# MCU.net
KiCad netlist of a schematic drawn in Altium Designer
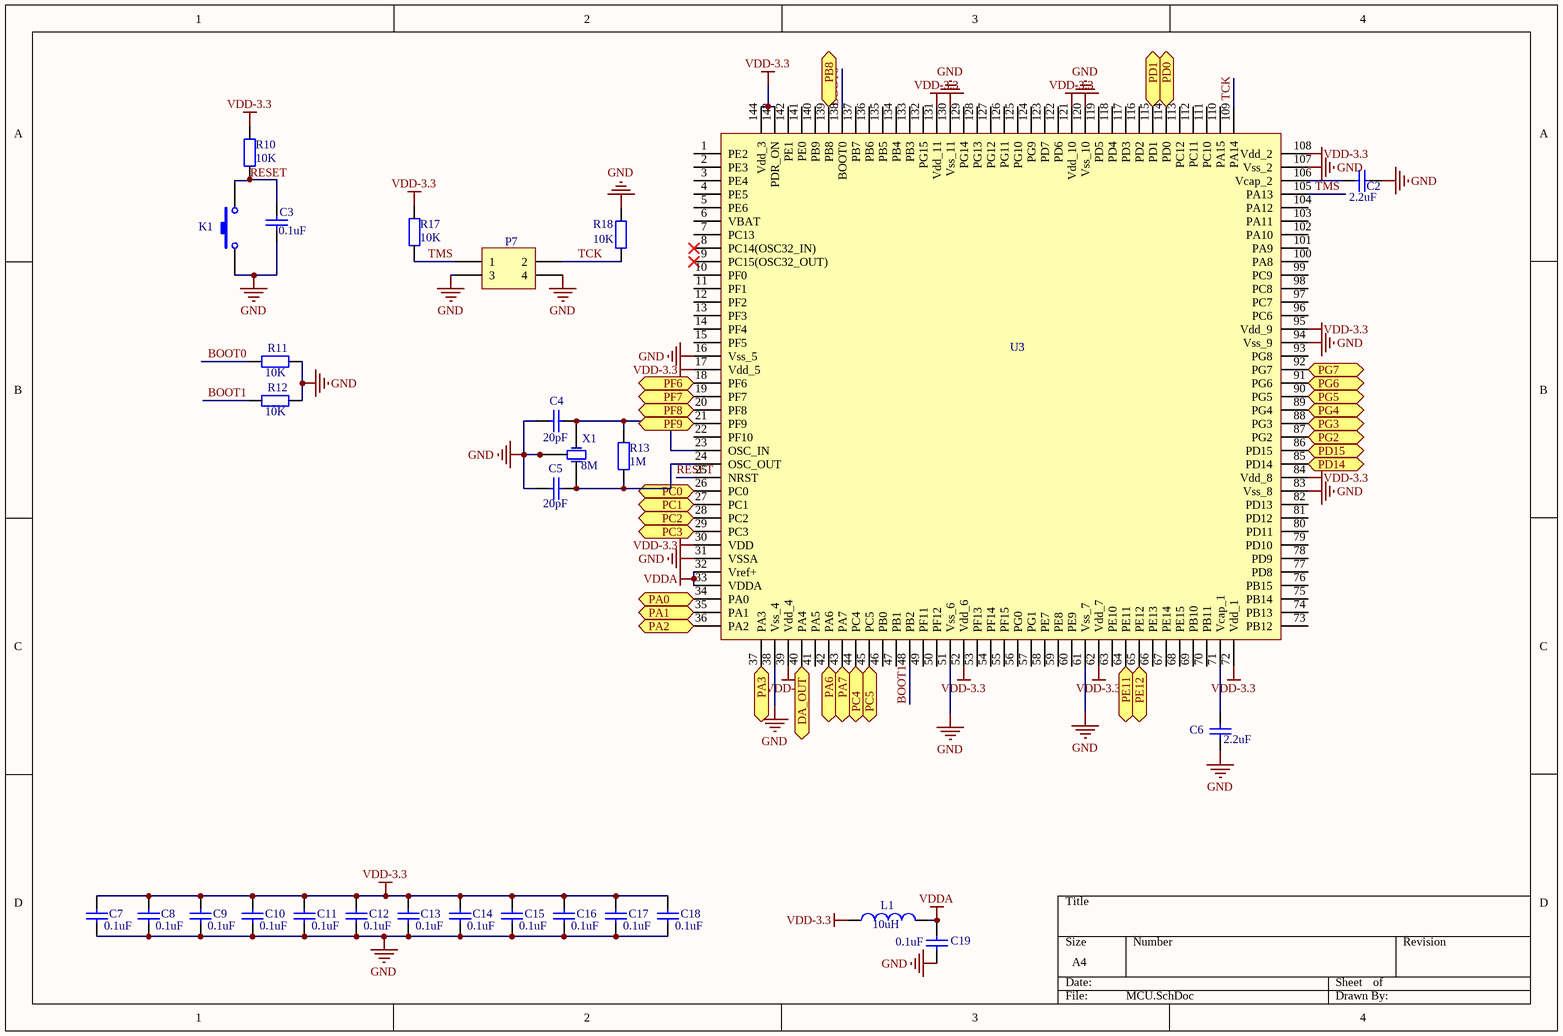
[diagram p0: MCU.SchDoc]

(export (version "E")
  (design (tool "Eeschema 10.0.6"))
  (components
    (comp (ref "C2")
      (value "2.2uF")
      (footprint "0603")
      (fields (field (name "Comment") "Capacitor-0603"))
      (libsource (lib "原理图库") (part "Capacitor-0603"))
    )
    (comp (ref "C3")
      (value "0.1uF")
      (footprint "0603")
      (fields (field (name "Comment") "Capacitor-0805"))
      (libsource (lib "原理图库") (part "Capacitor-0805"))
    )
    (comp (ref "C4")
      (value "20pF")
      (footprint "0603")
      (fields (field (name "Comment") "Capacitor-0603"))
      (libsource (lib "原理图库") (part "Capacitor-0603"))
    )
    (comp (ref "C5")
      (value "20pF")
      (footprint "0603")
      (fields (field (name "Comment") "Capacitor-0603"))
      (libsource (lib "原理图库") (part "Capacitor-0603"))
    )
    (comp (ref "C6")
      (value "2.2uF")
      (footprint "0603")
      (fields (field (name "Comment") "Capacitor-0603"))
      (libsource (lib "原理图库") (part "Capacitor-0603"))
    )
    (comp (ref "C7")
      (value "0.1uF")
      (footprint "0603")
      (fields (field (name "Comment") "Capacitor-0603"))
      (libsource (lib "原理图库") (part "Capacitor-0603"))
    )
    (comp (ref "C8")
      (value "0.1uF")
      (footprint "0603")
      (fields (field (name "Comment") "Capacitor-0603"))
      (libsource (lib "原理图库") (part "Capacitor-0603"))
    )
    (comp (ref "C9")
      (value "0.1uF")
      (footprint "0603")
      (fields (field (name "Comment") "Capacitor-0603"))
      (libsource (lib "原理图库") (part "Capacitor-0603"))
    )
    (comp (ref "C10")
      (value "0.1uF")
      (footprint "0603")
      (fields (field (name "Comment") "Capacitor-0603"))
      (libsource (lib "原理图库") (part "Capacitor-0603"))
    )
    (comp (ref "C11")
      (value "0.1uF")
      (footprint "0603")
      (fields (field (name "Comment") "Capacitor-0603"))
      (libsource (lib "原理图库") (part "Capacitor-0603"))
    )
    (comp (ref "C12")
      (value "0.1uF")
      (footprint "0603")
      (fields (field (name "Comment") "Capacitor-0603"))
      (libsource (lib "原理图库") (part "Capacitor-0603"))
    )
    (comp (ref "C13")
      (value "0.1uF")
      (footprint "0603")
      (fields (field (name "Comment") "Capacitor-0603"))
      (libsource (lib "原理图库") (part "Capacitor-0603"))
    )
    (comp (ref "C14")
      (value "0.1uF")
      (footprint "0603")
      (fields (field (name "Comment") "Capacitor-0603"))
      (libsource (lib "原理图库") (part "Capacitor-0603"))
    )
    (comp (ref "C15")
      (value "0.1uF")
      (footprint "0603")
      (fields (field (name "Comment") "Capacitor-0603"))
      (libsource (lib "原理图库") (part "Capacitor-0603"))
    )
    (comp (ref "C16")
      (value "0.1uF")
      (footprint "0603")
      (fields (field (name "Comment") "Capacitor-0603"))
      (libsource (lib "原理图库") (part "Capacitor-0603"))
    )
    (comp (ref "C17")
      (value "0.1uF")
      (footprint "0603")
      (fields (field (name "Comment") "Capacitor-0603"))
      (libsource (lib "原理图库") (part "Capacitor-0603"))
    )
    (comp (ref "C18")
      (value "0.1uF")
      (footprint "0603")
      (fields (field (name "Comment") "Capacitor-0603"))
      (libsource (lib "原理图库") (part "Capacitor-0603"))
    )
    (comp (ref "C19")
      (value "0.1uF")
      (footprint "0603")
      (fields (field (name "Comment") "Capacitor-0805"))
      (libsource (lib "集成库—大岐") (part "Capacitor-0805"))
    )
    (comp (ref "K1") (value "按键") (footprint "贴片按键") (libsource (lib "原理图库") (part "按键")))
    (comp (ref "L1")
      (value "10uH")
      (footprint "0805")
      (fields (field (name "Comment") "Inductor"))
      (libsource (lib "集成库—大岐") (part "Inductor"))
    )
    (comp (ref "P7")
      (value "Header 2X2")
      (footprint "HDR2X2")
      (description "Header, 2-Pin, Dual row")
      (fields (field (name "PUBLISHER") "Altium Limited"))
      (libsource (lib "Miscellaneous Connectors") (part "Header 2X2"))
    )
    (comp (ref "R10")
      (value "10K")
      (footprint "0603")
      (fields (field (name "Comment") "Resistor-0805"))
      (libsource (lib "") (part "Resistor-0805_1"))
    )
    (comp (ref "R11")
      (value "10K")
      (footprint "0603")
      (fields (field (name "Comment") "Resistor-0805"))
      (libsource (lib "") (part "Resistor-0805_2"))
    )
    (comp (ref "R12")
      (value "10K")
      (footprint "0603")
      (fields (field (name "Comment") "Resistor-0805"))
      (libsource (lib "") (part "Resistor-0805_2"))
    )
    (comp (ref "R13")
      (value "1M")
      (footprint "0603")
      (fields (field (name "Comment") "Resistor-0603"))
      (libsource (lib "原理图库") (part "Resistor-0603"))
    )
    (comp (ref "R17")
      (value "10K")
      (footprint "0603")
      (fields (field (name "Comment") "Resistor-0805"))
      (libsource (lib "原理图库") (part "Resistor-0805"))
    )
    (comp (ref "R18")
      (value "10K")
      (footprint "0603")
      (fields (field (name "Comment") "Resistor-0805"))
      (libsource (lib "") (part "Resistor-0805_1"))
    )
    (comp (ref "U3")
      (value "STM32F407ZET6")
      (footprint "Stm32f407ZET6 - duplicate")
      (fields (field (name "Comment") "STM32F407ZGT6"))
      (libsource (lib "原理图库") (part "STM32F407ZET6"))
    )
    (comp (ref "X1")
      (value "8M")
      (footprint "3225无源晶振")
      (fields (field (name "Comment") "3225无源晶振"))
      (libsource (lib "原理图库") (part "3225无源晶振"))
    )
  )
  (nets
    (net (code "1") (name "/BOOT0") (class "Default")
      (node (ref "R11") (pin "2") (pinfunction "2_2") (pintype "passive"))
      (node (ref "U3") (pin "138") (pinfunction "BOOT0_138") (pintype "passive"))
    )
    (net (code "2") (name "/BOOT1") (class "Default")
      (node (ref "R12") (pin "2") (pinfunction "2_2") (pintype "passive"))
      (node (ref "U3") (pin "48") (pinfunction "PB2_48") (pintype "passive"))
    )
    (net (code "3") (name "/DA_OUT") (class "Default")
      (node (ref "U3") (pin "40") (pinfunction "PA4_40") (pintype "passive"))
    )
    (net (code "4") (name "/PA0") (class "Default")
      (node (ref "U3") (pin "34") (pinfunction "PA0_34") (pintype "passive"))
    )
    (net (code "5") (name "/PA1") (class "Default")
      (node (ref "U3") (pin "35") (pinfunction "PA1_35") (pintype "passive"))
    )
    (net (code "6") (name "/PA2") (class "Default")
      (node (ref "U3") (pin "36") (pinfunction "PA2_36") (pintype "passive"))
    )
    (net (code "7") (name "/PA3") (class "Default")
      (node (ref "U3") (pin "37") (pinfunction "PA3_37") (pintype "passive"))
    )
    (net (code "8") (name "/PA6") (class "Default")
      (node (ref "U3") (pin "42") (pinfunction "PA6_42") (pintype "passive"))
    )
    (net (code "9") (name "/PA7") (class "Default")
      (node (ref "U3") (pin "43") (pinfunction "PA7_43") (pintype "passive"))
    )
    (net (code "10") (name "/PB8") (class "Default")
      (node (ref "U3") (pin "139") (pinfunction "PB8_139") (pintype "passive"))
    )
    (net (code "11") (name "/PC0") (class "Default")
      (node (ref "U3") (pin "26") (pinfunction "PC0_26") (pintype "passive"))
    )
    (net (code "12") (name "/PC1") (class "Default")
      (node (ref "U3") (pin "27") (pinfunction "PC1_27") (pintype "passive"))
    )
    (net (code "13") (name "/PC2") (class "Default")
      (node (ref "U3") (pin "28") (pinfunction "PC2_28") (pintype "passive"))
    )
    (net (code "14") (name "/PC3") (class "Default")
      (node (ref "U3") (pin "29") (pinfunction "PC3_29") (pintype "passive"))
    )
    (net (code "15") (name "/PC4") (class "Default")
      (node (ref "U3") (pin "44") (pinfunction "PC4_44") (pintype "passive"))
    )
    (net (code "16") (name "/PC5") (class "Default")
      (node (ref "U3") (pin "45") (pinfunction "PC5_45") (pintype "passive"))
    )
    (net (code "17") (name "/PD0") (class "Default")
      (node (ref "U3") (pin "114") (pinfunction "PD0_114") (pintype "passive"))
    )
    (net (code "18") (name "/PD1") (class "Default")
      (node (ref "U3") (pin "115") (pinfunction "PD1_115") (pintype "passive"))
    )
    (net (code "19") (name "/PD14") (class "Default")
      (node (ref "U3") (pin "85") (pinfunction "PD14_85") (pintype "passive"))
    )
    (net (code "20") (name "/PD15") (class "Default")
      (node (ref "U3") (pin "86") (pinfunction "PD15_86") (pintype "passive"))
    )
    (net (code "21") (name "/PE11") (class "Default")
      (node (ref "U3") (pin "64") (pinfunction "PE11_64") (pintype "passive"))
    )
    (net (code "22") (name "/PE12") (class "Default")
      (node (ref "U3") (pin "65") (pinfunction "PE12_65") (pintype "passive"))
    )
    (net (code "23") (name "/PF6") (class "Default")
      (node (ref "U3") (pin "18") (pinfunction "PF6_18") (pintype "passive"))
    )
    (net (code "24") (name "/PF7") (class "Default")
      (node (ref "U3") (pin "19") (pinfunction "PF7_19") (pintype "passive"))
    )
    (net (code "25") (name "/PF8") (class "Default")
      (node (ref "U3") (pin "20") (pinfunction "PF8_20") (pintype "passive"))
    )
    (net (code "26") (name "/PF9") (class "Default")
      (node (ref "U3") (pin "21") (pinfunction "PF9_21") (pintype "passive"))
    )
    (net (code "27") (name "/PG2") (class "Default")
      (node (ref "U3") (pin "87") (pinfunction "PG2_87") (pintype "passive"))
    )
    (net (code "28") (name "/PG3") (class "Default")
      (node (ref "U3") (pin "88") (pinfunction "PG3_88") (pintype "passive"))
    )
    (net (code "29") (name "/PG4") (class "Default")
      (node (ref "U3") (pin "89") (pinfunction "PG4_89") (pintype "passive"))
    )
    (net (code "30") (name "/PG5") (class "Default")
      (node (ref "U3") (pin "90") (pinfunction "PG5_90") (pintype "passive"))
    )
    (net (code "31") (name "/PG6") (class "Default")
      (node (ref "U3") (pin "91") (pinfunction "PG6_91") (pintype "passive"))
    )
    (net (code "32") (name "/PG7") (class "Default")
      (node (ref "U3") (pin "92") (pinfunction "PG7_92") (pintype "passive"))
    )
    (net (code "33") (name "/RESET") (class "Default")
      (node (ref "C3") (pin "2") (pinfunction "2_2") (pintype "passive"))
      (node (ref "K1") (pin "2") (pinfunction "2_2") (pintype "passive"))
      (node (ref "R10") (pin "1") (pinfunction "1_1") (pintype "passive"))
      (node (ref "U3") (pin "25") (pinfunction "NRST_25") (pintype "passive"))
    )
    (net (code "34") (name "/TCK") (class "Default")
      (node (ref "P7") (pin "2") (pinfunction "2_2") (pintype "passive"))
      (node (ref "R18") (pin "1") (pinfunction "1_1") (pintype "passive"))
      (node (ref "U3") (pin "109") (pinfunction "PA14_109") (pintype "passive"))
    )
    (net (code "35") (name "/TMS") (class "Default")
      (node (ref "P7") (pin "1") (pinfunction "1_1") (pintype "passive"))
      (node (ref "R17") (pin "2") (pinfunction "2_2") (pintype "passive"))
      (node (ref "U3") (pin "105") (pinfunction "PA13_105") (pintype "passive"))
    )
    (net (code "36") (name "GND") (class "Default")
      (node (ref "C10") (pin "1") (pinfunction "1_1") (pintype "passive"))
      (node (ref "C11") (pin "1") (pinfunction "1_1") (pintype "passive"))
      (node (ref "C12") (pin "1") (pinfunction "1_1") (pintype "passive"))
      (node (ref "C13") (pin "1") (pinfunction "1_1") (pintype "passive"))
      (node (ref "C14") (pin "1") (pinfunction "1_1") (pintype "passive"))
      (node (ref "C15") (pin "1") (pinfunction "1_1") (pintype "passive"))
      (node (ref "C16") (pin "1") (pinfunction "1_1") (pintype "passive"))
      (node (ref "C17") (pin "1") (pinfunction "1_1") (pintype "passive"))
      (node (ref "C18") (pin "1") (pinfunction "1_1") (pintype "passive"))
      (node (ref "C19") (pin "1") (pinfunction "1_1") (pintype "passive"))
      (node (ref "C2") (pin "2") (pinfunction "2_2") (pintype "passive"))
      (node (ref "C3") (pin "1") (pinfunction "1_1") (pintype "passive"))
      (node (ref "C4") (pin "1") (pinfunction "1_1") (pintype "passive"))
      (node (ref "C5") (pin "1") (pinfunction "1_1") (pintype "passive"))
      (node (ref "C6") (pin "1") (pinfunction "1_1") (pintype "passive"))
      (node (ref "C7") (pin "1") (pinfunction "1_1") (pintype "passive"))
      (node (ref "C8") (pin "1") (pinfunction "1_1") (pintype "passive"))
      (node (ref "C9") (pin "1") (pinfunction "1_1") (pintype "passive"))
      (node (ref "K1") (pin "1") (pinfunction "1_1") (pintype "passive"))
      (node (ref "P7") (pin "3") (pinfunction "3_3") (pintype "passive"))
      (node (ref "P7") (pin "4") (pinfunction "4_4") (pintype "passive"))
      (node (ref "R11") (pin "1") (pinfunction "1_1") (pintype "passive"))
      (node (ref "R12") (pin "1") (pinfunction "1_1") (pintype "passive"))
      (node (ref "R18") (pin "2") (pinfunction "2_2") (pintype "passive"))
      (node (ref "U3") (pin "107") (pinfunction "Vss_2_107") (pintype "passive"))
      (node (ref "U3") (pin "120") (pinfunction "Vss_10_120") (pintype "passive"))
      (node (ref "U3") (pin "130") (pinfunction "Vss_11_130") (pintype "passive"))
      (node (ref "U3") (pin "16") (pinfunction "Vss_5_16") (pintype "passive"))
      (node (ref "U3") (pin "31") (pinfunction "VSSA_31") (pintype "passive"))
      (node (ref "U3") (pin "38") (pinfunction "Vss_4_38") (pintype "passive"))
      (node (ref "U3") (pin "51") (pinfunction "Vss_6_51") (pintype "passive"))
      (node (ref "U3") (pin "61") (pinfunction "Vss_7_61") (pintype "passive"))
      (node (ref "U3") (pin "83") (pinfunction "Vss_8_83") (pintype "passive"))
      (node (ref "U3") (pin "94") (pinfunction "Vss_9_94") (pintype "passive"))
      (node (ref "X1") (pin "2") (pinfunction "GND_2") (pintype "passive"))
      (node (ref "X1") (pin "4") (pinfunction "GND_4") (pintype "passive"))
    )
    (net (code "37") (name "Net-(U3-OSC_IN)") (class "Default")
      (node (ref "C4") (pin "2") (pinfunction "2_2") (pintype "passive"))
      (node (ref "R13") (pin "2") (pinfunction "2_2") (pintype "passive"))
      (node (ref "U3") (pin "23") (pinfunction "OSC_IN_23") (pintype "passive"))
      (node (ref "X1") (pin "1") (pinfunction "OSC1_1") (pintype "passive"))
    )
    (net (code "38") (name "Net-(U3-OSC_OUT)") (class "Default")
      (node (ref "C5") (pin "2") (pinfunction "2_2") (pintype "passive"))
      (node (ref "R13") (pin "1") (pinfunction "1_1") (pintype "passive"))
      (node (ref "U3") (pin "24") (pinfunction "OSC_OUT_24") (pintype "passive"))
      (node (ref "X1") (pin "3") (pinfunction "OSC2_3") (pintype "passive"))
    )
    (net (code "39") (name "Net-(U3-Vcap_1)") (class "Default")
      (node (ref "C6") (pin "2") (pinfunction "2_2") (pintype "passive"))
      (node (ref "U3") (pin "71") (pinfunction "Vcap_1_71") (pintype "passive"))
    )
    (net (code "40") (name "Net-(U3-Vcap_2)") (class "Default")
      (node (ref "C2") (pin "1") (pinfunction "1_1") (pintype "passive"))
      (node (ref "U3") (pin "106") (pinfunction "Vcap_2_106") (pintype "passive"))
    )
    (net (code "41") (name "VDD-3.3") (class "Default")
      (node (ref "C10") (pin "2") (pinfunction "2_2") (pintype "passive"))
      (node (ref "C11") (pin "2") (pinfunction "2_2") (pintype "passive"))
      (node (ref "C12") (pin "2") (pinfunction "2_2") (pintype "passive"))
      (node (ref "C13") (pin "2") (pinfunction "2_2") (pintype "passive"))
      (node (ref "C14") (pin "2") (pinfunction "2_2") (pintype "passive"))
      (node (ref "C15") (pin "2") (pinfunction "2_2") (pintype "passive"))
      (node (ref "C16") (pin "2") (pinfunction "2_2") (pintype "passive"))
      (node (ref "C17") (pin "2") (pinfunction "2_2") (pintype "passive"))
      (node (ref "C18") (pin "2") (pinfunction "2_2") (pintype "passive"))
      (node (ref "C7") (pin "2") (pinfunction "2_2") (pintype "passive"))
      (node (ref "C8") (pin "2") (pinfunction "2_2") (pintype "passive"))
      (node (ref "C9") (pin "2") (pinfunction "2_2") (pintype "passive"))
      (node (ref "L1") (pin "1") (pinfunction "1_1") (pintype "passive"))
      (node (ref "R10") (pin "2") (pinfunction "2_2") (pintype "passive"))
      (node (ref "R17") (pin "1") (pinfunction "1_1") (pintype "passive"))
      (node (ref "U3") (pin "108") (pinfunction "Vdd_2_108") (pintype "passive"))
      (node (ref "U3") (pin "121") (pinfunction "Vdd_10_121") (pintype "passive"))
      (node (ref "U3") (pin "131") (pinfunction "Vdd_11_131") (pintype "passive"))
      (node (ref "U3") (pin "143") (pinfunction "PDR_ON_143") (pintype "passive"))
      (node (ref "U3") (pin "144") (pinfunction "Vdd_3_144") (pintype "passive"))
      (node (ref "U3") (pin "17") (pinfunction "Vdd_5_17") (pintype "passive"))
      (node (ref "U3") (pin "30") (pinfunction "VDD_30") (pintype "passive"))
      (node (ref "U3") (pin "39") (pinfunction "Vdd_4_39") (pintype "passive"))
      (node (ref "U3") (pin "52") (pinfunction "Vdd_6_52") (pintype "passive"))
      (node (ref "U3") (pin "62") (pinfunction "Vdd_7_62") (pintype "passive"))
      (node (ref "U3") (pin "72") (pinfunction "Vdd_1_72") (pintype "passive"))
      (node (ref "U3") (pin "84") (pinfunction "Vdd_8_84") (pintype "passive"))
      (node (ref "U3") (pin "95") (pinfunction "Vdd_9_95") (pintype "passive"))
    )
    (net (code "42") (name "VDDA") (class "Default")
      (node (ref "C19") (pin "2") (pinfunction "2_2") (pintype "passive"))
      (node (ref "L1") (pin "2") (pinfunction "2_2") (pintype "passive"))
      (node (ref "U3") (pin "32") (pinfunction "Vref+_32") (pintype "passive"))
      (node (ref "U3") (pin "33") (pinfunction "VDDA_33") (pintype "passive"))
    )
    (net (code "43") (name "unconnected-(U3-PA5-Pad41)") (class "Default")
      (node (ref "U3") (pin "41") (pinfunction "PA5_41") (pintype "passive"))
    )
    (net (code "44") (name "unconnected-(U3-PA8-Pad100)") (class "Default")
      (node (ref "U3") (pin "100") (pinfunction "PA8_100") (pintype "passive"))
    )
    (net (code "45") (name "unconnected-(U3-PA9-Pad101)") (class "Default")
      (node (ref "U3") (pin "101") (pinfunction "PA9_101") (pintype "passive"))
    )
    (net (code "46") (name "unconnected-(U3-PA10-Pad102)") (class "Default")
      (node (ref "U3") (pin "102") (pinfunction "PA10_102") (pintype "passive"))
    )
    (net (code "47") (name "unconnected-(U3-PA11-Pad103)") (class "Default")
      (node (ref "U3") (pin "103") (pinfunction "PA11_103") (pintype "passive"))
    )
    (net (code "48") (name "unconnected-(U3-PA12-Pad104)") (class "Default")
      (node (ref "U3") (pin "104") (pinfunction "PA12_104") (pintype "passive"))
    )
    (net (code "49") (name "unconnected-(U3-PA15-Pad110)") (class "Default")
      (node (ref "U3") (pin "110") (pinfunction "PA15_110") (pintype "passive"))
    )
    (net (code "50") (name "unconnected-(U3-PB0-Pad46)") (class "Default")
      (node (ref "U3") (pin "46") (pinfunction "PB0_46") (pintype "passive"))
    )
    (net (code "51") (name "unconnected-(U3-PB1-Pad47)") (class "Default")
      (node (ref "U3") (pin "47") (pinfunction "PB1_47") (pintype "passive"))
    )
    (net (code "52") (name "unconnected-(U3-PB3-Pad133)") (class "Default")
      (node (ref "U3") (pin "133") (pinfunction "PB3_133") (pintype "passive"))
    )
    (net (code "53") (name "unconnected-(U3-PB4-Pad134)") (class "Default")
      (node (ref "U3") (pin "134") (pinfunction "PB4_134") (pintype "passive"))
    )
    (net (code "54") (name "unconnected-(U3-PB5-Pad135)") (class "Default")
      (node (ref "U3") (pin "135") (pinfunction "PB5_135") (pintype "passive"))
    )
    (net (code "55") (name "unconnected-(U3-PB6-Pad136)") (class "Default")
      (node (ref "U3") (pin "136") (pinfunction "PB6_136") (pintype "passive"))
    )
    (net (code "56") (name "unconnected-(U3-PB7-Pad137)") (class "Default")
      (node (ref "U3") (pin "137") (pinfunction "PB7_137") (pintype "passive"))
    )
    (net (code "57") (name "unconnected-(U3-PB9-Pad140)") (class "Default")
      (node (ref "U3") (pin "140") (pinfunction "PB9_140") (pintype "passive"))
    )
    (net (code "58") (name "unconnected-(U3-PB10-Pad69)") (class "Default")
      (node (ref "U3") (pin "69") (pinfunction "PB10_69") (pintype "passive"))
    )
    (net (code "59") (name "unconnected-(U3-PB11-Pad70)") (class "Default")
      (node (ref "U3") (pin "70") (pinfunction "PB11_70") (pintype "passive"))
    )
    (net (code "60") (name "unconnected-(U3-PB12-Pad73)") (class "Default")
      (node (ref "U3") (pin "73") (pinfunction "PB12_73") (pintype "passive"))
    )
    (net (code "61") (name "unconnected-(U3-PB13-Pad74)") (class "Default")
      (node (ref "U3") (pin "74") (pinfunction "PB13_74") (pintype "passive"))
    )
    (net (code "62") (name "unconnected-(U3-PB14-Pad75)") (class "Default")
      (node (ref "U3") (pin "75") (pinfunction "PB14_75") (pintype "passive"))
    )
    (net (code "63") (name "unconnected-(U3-PB15-Pad76)") (class "Default")
      (node (ref "U3") (pin "76") (pinfunction "PB15_76") (pintype "passive"))
    )
    (net (code "64") (name "unconnected-(U3-PC6-Pad96)") (class "Default")
      (node (ref "U3") (pin "96") (pinfunction "PC6_96") (pintype "passive"))
    )
    (net (code "65") (name "unconnected-(U3-PC7-Pad97)") (class "Default")
      (node (ref "U3") (pin "97") (pinfunction "PC7_97") (pintype "passive"))
    )
    (net (code "66") (name "unconnected-(U3-PC8-Pad98)") (class "Default")
      (node (ref "U3") (pin "98") (pinfunction "PC8_98") (pintype "passive"))
    )
    (net (code "67") (name "unconnected-(U3-PC9-Pad99)") (class "Default")
      (node (ref "U3") (pin "99") (pinfunction "PC9_99") (pintype "passive"))
    )
    (net (code "68") (name "unconnected-(U3-PC10-Pad111)") (class "Default")
      (node (ref "U3") (pin "111") (pinfunction "PC10_111") (pintype "passive"))
    )
    (net (code "69") (name "unconnected-(U3-PC11-Pad112)") (class "Default")
      (node (ref "U3") (pin "112") (pinfunction "PC11_112") (pintype "passive"))
    )
    (net (code "70") (name "unconnected-(U3-PC12-Pad113)") (class "Default")
      (node (ref "U3") (pin "113") (pinfunction "PC12_113") (pintype "passive"))
    )
    (net (code "71") (name "unconnected-(U3-PC13-Pad7)") (class "Default")
      (node (ref "U3") (pin "7") (pinfunction "PC13_7") (pintype "passive"))
    )
    (net (code "72") (name "unconnected-(U3-PC14(OSC32_IN)-Pad8)") (class "Default")
      (node (ref "U3") (pin "8") (pinfunction "PC14(OSC32_IN)_8") (pintype "passive+no_connect"))
    )
    (net (code "73") (name "unconnected-(U3-PC15(OSC32_OUT)-Pad9)") (class "Default")
      (node (ref "U3") (pin "9") (pinfunction "PC15(OSC32_OUT)_9") (pintype "passive+no_connect"))
    )
    (net (code "74") (name "unconnected-(U3-PD2-Pad116)") (class "Default")
      (node (ref "U3") (pin "116") (pinfunction "PD2_116") (pintype "passive"))
    )
    (net (code "75") (name "unconnected-(U3-PD3-Pad117)") (class "Default")
      (node (ref "U3") (pin "117") (pinfunction "PD3_117") (pintype "passive"))
    )
    (net (code "76") (name "unconnected-(U3-PD4-Pad118)") (class "Default")
      (node (ref "U3") (pin "118") (pinfunction "PD4_118") (pintype "passive"))
    )
    (net (code "77") (name "unconnected-(U3-PD5-Pad119)") (class "Default")
      (node (ref "U3") (pin "119") (pinfunction "PD5_119") (pintype "passive"))
    )
    (net (code "78") (name "unconnected-(U3-PD6-Pad122)") (class "Default")
      (node (ref "U3") (pin "122") (pinfunction "PD6_122") (pintype "passive"))
    )
    (net (code "79") (name "unconnected-(U3-PD7-Pad123)") (class "Default")
      (node (ref "U3") (pin "123") (pinfunction "PD7_123") (pintype "passive"))
    )
    (net (code "80") (name "unconnected-(U3-PD8-Pad77)") (class "Default")
      (node (ref "U3") (pin "77") (pinfunction "PD8_77") (pintype "passive"))
    )
    (net (code "81") (name "unconnected-(U3-PD9-Pad78)") (class "Default")
      (node (ref "U3") (pin "78") (pinfunction "PD9_78") (pintype "passive"))
    )
    (net (code "82") (name "unconnected-(U3-PD10-Pad79)") (class "Default")
      (node (ref "U3") (pin "79") (pinfunction "PD10_79") (pintype "passive"))
    )
    (net (code "83") (name "unconnected-(U3-PD11-Pad80)") (class "Default")
      (node (ref "U3") (pin "80") (pinfunction "PD11_80") (pintype "passive"))
    )
    (net (code "84") (name "unconnected-(U3-PD12-Pad81)") (class "Default")
      (node (ref "U3") (pin "81") (pinfunction "PD12_81") (pintype "passive"))
    )
    (net (code "85") (name "unconnected-(U3-PD13-Pad82)") (class "Default")
      (node (ref "U3") (pin "82") (pinfunction "PD13_82") (pintype "passive"))
    )
    (net (code "86") (name "unconnected-(U3-PE0-Pad141)") (class "Default")
      (node (ref "U3") (pin "141") (pinfunction "PE0_141") (pintype "passive"))
    )
    (net (code "87") (name "unconnected-(U3-PE1-Pad142)") (class "Default")
      (node (ref "U3") (pin "142") (pinfunction "PE1_142") (pintype "passive"))
    )
    (net (code "88") (name "unconnected-(U3-PE2-Pad1)") (class "Default")
      (node (ref "U3") (pin "1") (pinfunction "PE2_1") (pintype "passive"))
    )
    (net (code "89") (name "unconnected-(U3-PE3-Pad2)") (class "Default")
      (node (ref "U3") (pin "2") (pinfunction "PE3_2") (pintype "passive"))
    )
    (net (code "90") (name "unconnected-(U3-PE4-Pad3)") (class "Default")
      (node (ref "U3") (pin "3") (pinfunction "PE4_3") (pintype "passive"))
    )
    (net (code "91") (name "unconnected-(U3-PE5-Pad4)") (class "Default")
      (node (ref "U3") (pin "4") (pinfunction "PE5_4") (pintype "passive"))
    )
    (net (code "92") (name "unconnected-(U3-PE6-Pad5)") (class "Default")
      (node (ref "U3") (pin "5") (pinfunction "PE6_5") (pintype "passive"))
    )
    (net (code "93") (name "unconnected-(U3-PE7-Pad58)") (class "Default")
      (node (ref "U3") (pin "58") (pinfunction "PE7_58") (pintype "passive"))
    )
    (net (code "94") (name "unconnected-(U3-PE8-Pad59)") (class "Default")
      (node (ref "U3") (pin "59") (pinfunction "PE8_59") (pintype "passive"))
    )
    (net (code "95") (name "unconnected-(U3-PE9-Pad60)") (class "Default")
      (node (ref "U3") (pin "60") (pinfunction "PE9_60") (pintype "passive"))
    )
    (net (code "96") (name "unconnected-(U3-PE10-Pad63)") (class "Default")
      (node (ref "U3") (pin "63") (pinfunction "PE10_63") (pintype "passive"))
    )
    (net (code "97") (name "unconnected-(U3-PE13-Pad66)") (class "Default")
      (node (ref "U3") (pin "66") (pinfunction "PE13_66") (pintype "passive"))
    )
    (net (code "98") (name "unconnected-(U3-PE14-Pad67)") (class "Default")
      (node (ref "U3") (pin "67") (pinfunction "PE14_67") (pintype "passive"))
    )
    (net (code "99") (name "unconnected-(U3-PE15-Pad68)") (class "Default")
      (node (ref "U3") (pin "68") (pinfunction "PE15_68") (pintype "passive"))
    )
    (net (code "100") (name "unconnected-(U3-PF0-Pad10)") (class "Default")
      (node (ref "U3") (pin "10") (pinfunction "PF0_10") (pintype "passive"))
    )
    (net (code "101") (name "unconnected-(U3-PF1-Pad11)") (class "Default")
      (node (ref "U3") (pin "11") (pinfunction "PF1_11") (pintype "passive"))
    )
    (net (code "102") (name "unconnected-(U3-PF2-Pad12)") (class "Default")
      (node (ref "U3") (pin "12") (pinfunction "PF2_12") (pintype "passive"))
    )
    (net (code "103") (name "unconnected-(U3-PF3-Pad13)") (class "Default")
      (node (ref "U3") (pin "13") (pinfunction "PF3_13") (pintype "passive"))
    )
    (net (code "104") (name "unconnected-(U3-PF4-Pad14)") (class "Default")
      (node (ref "U3") (pin "14") (pinfunction "PF4_14") (pintype "passive"))
    )
    (net (code "105") (name "unconnected-(U3-PF5-Pad15)") (class "Default")
      (node (ref "U3") (pin "15") (pinfunction "PF5_15") (pintype "passive"))
    )
    (net (code "106") (name "unconnected-(U3-PF10-Pad22)") (class "Default")
      (node (ref "U3") (pin "22") (pinfunction "PF10_22") (pintype "passive"))
    )
    (net (code "107") (name "unconnected-(U3-PF11-Pad49)") (class "Default")
      (node (ref "U3") (pin "49") (pinfunction "PF11_49") (pintype "passive"))
    )
    (net (code "108") (name "unconnected-(U3-PF12-Pad50)") (class "Default")
      (node (ref "U3") (pin "50") (pinfunction "PF12_50") (pintype "passive"))
    )
    (net (code "109") (name "unconnected-(U3-PF13-Pad53)") (class "Default")
      (node (ref "U3") (pin "53") (pinfunction "PF13_53") (pintype "passive"))
    )
    (net (code "110") (name "unconnected-(U3-PF14-Pad54)") (class "Default")
      (node (ref "U3") (pin "54") (pinfunction "PF14_54") (pintype "passive"))
    )
    (net (code "111") (name "unconnected-(U3-PF15-Pad55)") (class "Default")
      (node (ref "U3") (pin "55") (pinfunction "PF15_55") (pintype "passive"))
    )
    (net (code "112") (name "unconnected-(U3-PG0-Pad56)") (class "Default")
      (node (ref "U3") (pin "56") (pinfunction "PG0_56") (pintype "passive"))
    )
    (net (code "113") (name "unconnected-(U3-PG1-Pad57)") (class "Default")
      (node (ref "U3") (pin "57") (pinfunction "PG1_57") (pintype "passive"))
    )
    (net (code "114") (name "unconnected-(U3-PG8-Pad93)") (class "Default")
      (node (ref "U3") (pin "93") (pinfunction "PG8_93") (pintype "passive"))
    )
    (net (code "115") (name "unconnected-(U3-PG9-Pad124)") (class "Default")
      (node (ref "U3") (pin "124") (pinfunction "PG9_124") (pintype "passive"))
    )
    (net (code "116") (name "unconnected-(U3-PG10-Pad125)") (class "Default")
      (node (ref "U3") (pin "125") (pinfunction "PG10_125") (pintype "passive"))
    )
    (net (code "117") (name "unconnected-(U3-PG11-Pad126)") (class "Default")
      (node (ref "U3") (pin "126") (pinfunction "PG11_126") (pintype "passive"))
    )
    (net (code "118") (name "unconnected-(U3-PG12-Pad127)") (class "Default")
      (node (ref "U3") (pin "127") (pinfunction "PG12_127") (pintype "passive"))
    )
    (net (code "119") (name "unconnected-(U3-PG13-Pad128)") (class "Default")
      (node (ref "U3") (pin "128") (pinfunction "PG13_128") (pintype "passive"))
    )
    (net (code "120") (name "unconnected-(U3-PG14-Pad129)") (class "Default")
      (node (ref "U3") (pin "129") (pinfunction "PG14_129") (pintype "passive"))
    )
    (net (code "121") (name "unconnected-(U3-PG15-Pad132)") (class "Default")
      (node (ref "U3") (pin "132") (pinfunction "PG15_132") (pintype "passive"))
    )
    (net (code "122") (name "unconnected-(U3-VBAT-Pad6)") (class "Default")
      (node (ref "U3") (pin "6") (pinfunction "VBAT_6") (pintype "passive"))
    )
  )
)
